# arduino_connector.net
KiCad netlist of a schematic drawn in Altium Designer
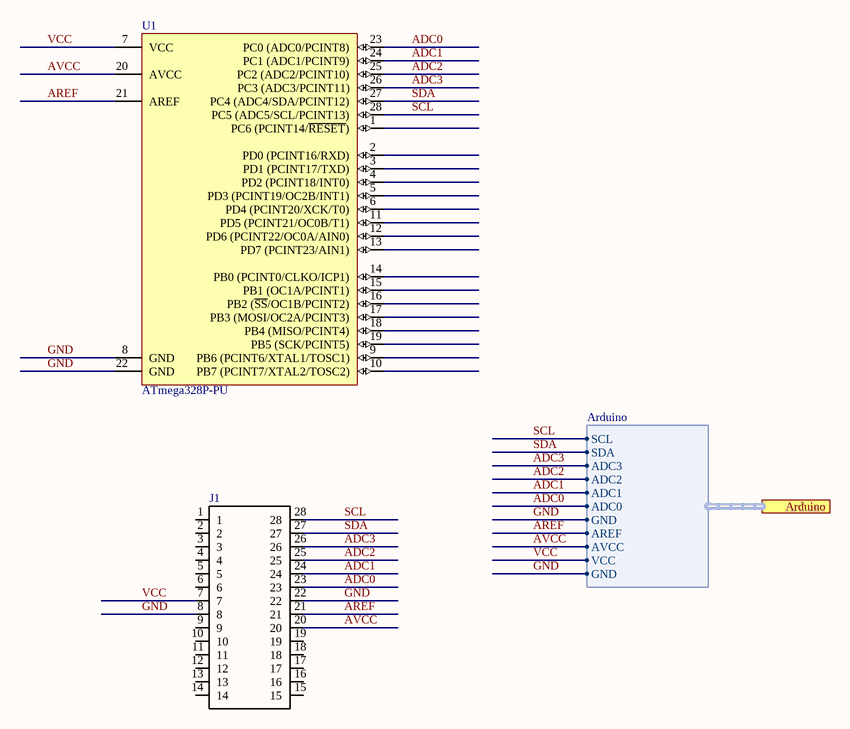
[diagram p0: arduino_connector.SchDoc]

(export (version "E")
  (design (tool "Eeschema 10.0.6"))
  (components
    (comp (ref "J1")
      (value "1-2199298-9")
      (footprint "*DIP762W60P254L3556H510Q28")
      (description "28P,DIP SKT,300 CL,LDR,PB FREE")
      (fields (field (name "DIGI-KEY_PART_NUMBER") "A120353-ND") (field (name "MF") "TE Connectivity"))
      (libsource (lib "1-2199298-9") (part "1-2199298-9"))
    )
    (comp (ref "U1")
      (value "ATmega328P-PU")
      (footprint "28P3")
      (libsource (lib "Altium Content Vault") (part "MC-8B-ATM48-IL28"))
    )
  )
  (nets
    (net (code "2") (name "/ADC0") (class "Default")
      (node (ref "J1") (pin "23") (pinfunction "23_23") (pintype "passive"))
      (node (ref "U1") (pin "23") (pinfunction "PC0_(ADC0/PCINT8)_23") (pintype "bidirectional"))
    )
    (net (code "3") (name "/ADC1") (class "Default")
      (node (ref "J1") (pin "24") (pinfunction "24_24") (pintype "passive"))
      (node (ref "U1") (pin "24") (pinfunction "PC1_(ADC1/PCINT9)_24") (pintype "bidirectional"))
    )
    (net (code "4") (name "/ADC2") (class "Default")
      (node (ref "J1") (pin "25") (pinfunction "25_25") (pintype "passive"))
      (node (ref "U1") (pin "25") (pinfunction "PC2_(ADC2/PCINT10)_25") (pintype "bidirectional"))
    )
    (net (code "5") (name "/ADC3") (class "Default")
      (node (ref "J1") (pin "26") (pinfunction "26_26") (pintype "passive"))
      (node (ref "U1") (pin "26") (pinfunction "PC3_(ADC3/PCINT11)_26") (pintype "bidirectional"))
    )
    (net (code "6") (name "/AREF") (class "Default")
      (node (ref "J1") (pin "21") (pinfunction "21_21") (pintype "passive"))
      (node (ref "U1") (pin "21") (pinfunction "AREF_21") (pintype "power_in"))
    )
    (net (code "7") (name "/AVCC") (class "Default")
      (node (ref "J1") (pin "20") (pinfunction "20_20") (pintype "passive"))
      (node (ref "U1") (pin "20") (pinfunction "AVCC_20") (pintype "power_in"))
    )
    (net (code "8") (name "/GND") (class "Default")
      (node (ref "J1") (pin "22") (pinfunction "22_22") (pintype "passive"))
      (node (ref "J1") (pin "8") (pinfunction "8_8") (pintype "passive"))
      (node (ref "U1") (pin "22") (pinfunction "GND_22") (pintype "power_in"))
      (node (ref "U1") (pin "8") (pinfunction "GND_8") (pintype "power_in"))
    )
    (net (code "9") (name "/SCL") (class "Default")
      (node (ref "J1") (pin "28") (pinfunction "28_28") (pintype "passive"))
      (node (ref "U1") (pin "28") (pinfunction "PC5_(ADC5/SCL/PCINT13)_28") (pintype "bidirectional"))
    )
    (net (code "10") (name "/SDA") (class "Default")
      (node (ref "J1") (pin "27") (pinfunction "27_27") (pintype "passive"))
      (node (ref "U1") (pin "27") (pinfunction "PC4_(ADC4/SDA/PCINT12)_27") (pintype "bidirectional"))
    )
    (net (code "11") (name "/VCC") (class "Default")
      (node (ref "J1") (pin "7") (pinfunction "7_7") (pintype "passive"))
      (node (ref "U1") (pin "7") (pinfunction "VCC_7") (pintype "power_in"))
    )
    (net (code "13") (name "unconnected-(J1-Pad1)") (class "Default")
      (node (ref "J1") (pin "1") (pinfunction "1_1") (pintype "passive"))
    )
    (net (code "14") (name "unconnected-(J1-Pad2)") (class "Default")
      (node (ref "J1") (pin "2") (pinfunction "2_2") (pintype "passive"))
    )
    (net (code "15") (name "unconnected-(J1-Pad3)") (class "Default")
      (node (ref "J1") (pin "3") (pinfunction "3_3") (pintype "passive"))
    )
    (net (code "16") (name "unconnected-(J1-Pad4)") (class "Default")
      (node (ref "J1") (pin "4") (pinfunction "4_4") (pintype "passive"))
    )
    (net (code "17") (name "unconnected-(J1-Pad5)") (class "Default")
      (node (ref "J1") (pin "5") (pinfunction "5_5") (pintype "passive"))
    )
    (net (code "18") (name "unconnected-(J1-Pad6)") (class "Default")
      (node (ref "J1") (pin "6") (pinfunction "6_6") (pintype "passive"))
    )
    (net (code "19") (name "unconnected-(J1-Pad9)") (class "Default")
      (node (ref "J1") (pin "9") (pinfunction "9_9") (pintype "passive"))
    )
    (net (code "20") (name "unconnected-(J1-Pad10)") (class "Default")
      (node (ref "J1") (pin "10") (pinfunction "10_10") (pintype "passive"))
    )
    (net (code "21") (name "unconnected-(J1-Pad11)") (class "Default")
      (node (ref "J1") (pin "11") (pinfunction "11_11") (pintype "passive"))
    )
    (net (code "22") (name "unconnected-(J1-Pad12)") (class "Default")
      (node (ref "J1") (pin "12") (pinfunction "12_12") (pintype "passive"))
    )
    (net (code "23") (name "unconnected-(J1-Pad13)") (class "Default")
      (node (ref "J1") (pin "13") (pinfunction "13_13") (pintype "passive"))
    )
    (net (code "24") (name "unconnected-(J1-Pad14)") (class "Default")
      (node (ref "J1") (pin "14") (pinfunction "14_14") (pintype "passive"))
    )
    (net (code "25") (name "unconnected-(J1-Pad15)") (class "Default")
      (node (ref "J1") (pin "15") (pinfunction "15_15") (pintype "passive"))
    )
    (net (code "26") (name "unconnected-(J1-Pad16)") (class "Default")
      (node (ref "J1") (pin "16") (pinfunction "16_16") (pintype "passive"))
    )
    (net (code "27") (name "unconnected-(J1-Pad17)") (class "Default")
      (node (ref "J1") (pin "17") (pinfunction "17_17") (pintype "passive"))
    )
    (net (code "28") (name "unconnected-(J1-Pad18)") (class "Default")
      (node (ref "J1") (pin "18") (pinfunction "18_18") (pintype "passive"))
    )
    (net (code "29") (name "unconnected-(J1-Pad19)") (class "Default")
      (node (ref "J1") (pin "19") (pinfunction "19_19") (pintype "passive"))
    )
    (net (code "30") (name "unconnected-(U1-PB0_(PCINT0{slash}CLKO{slash}ICP1)-Pad14)") (class "Default")
      (node (ref "U1") (pin "14") (pinfunction "PB0_(PCINT0/CLKO/ICP1)_14") (pintype "bidirectional"))
    )
    (net (code "31") (name "unconnected-(U1-PB1_(OC1A{slash}PCINT1)-Pad15)") (class "Default")
      (node (ref "U1") (pin "15") (pinfunction "PB1_(OC1A/PCINT1)_15") (pintype "bidirectional"))
    )
    (net (code "32") (name "unconnected-(U1-PB2_(~{SS}{slash}OC1B{slash}PCINT2)-Pad16)") (class "Default")
      (node (ref "U1") (pin "16") (pinfunction "PB2_(~{SS}/OC1B/PCINT2)_16") (pintype "bidirectional"))
    )
    (net (code "33") (name "unconnected-(U1-PB3_(MOSI{slash}OC2A{slash}PCINT3)-Pad17)") (class "Default")
      (node (ref "U1") (pin "17") (pinfunction "PB3_(MOSI/OC2A/PCINT3)_17") (pintype "bidirectional"))
    )
    (net (code "34") (name "unconnected-(U1-PB4_(MISO{slash}PCINT4)-Pad18)") (class "Default")
      (node (ref "U1") (pin "18") (pinfunction "PB4_(MISO/PCINT4)_18") (pintype "bidirectional"))
    )
    (net (code "35") (name "unconnected-(U1-PB5_(SCK{slash}PCINT5)-Pad19)") (class "Default")
      (node (ref "U1") (pin "19") (pinfunction "PB5_(SCK/PCINT5)_19") (pintype "bidirectional"))
    )
    (net (code "36") (name "unconnected-(U1-PB6_(PCINT6{slash}XTAL1{slash}TOSC1)-Pad9)") (class "Default")
      (node (ref "U1") (pin "9") (pinfunction "PB6_(PCINT6/XTAL1/TOSC1)_9") (pintype "bidirectional"))
    )
    (net (code "37") (name "unconnected-(U1-PB7_(PCINT7{slash}XTAL2{slash}TOSC2)-Pad10)") (class "Default")
      (node (ref "U1") (pin "10") (pinfunction "PB7_(PCINT7/XTAL2/TOSC2)_10") (pintype "bidirectional"))
    )
    (net (code "38") (name "unconnected-(U1-PC6_(PCINT14{slash}~{RESET})-Pad1)") (class "Default")
      (node (ref "U1") (pin "1") (pinfunction "PC6_(PCINT14/~{RESET})_1") (pintype "bidirectional"))
    )
    (net (code "39") (name "unconnected-(U1-PD0_(PCINT16{slash}RXD)-Pad2)") (class "Default")
      (node (ref "U1") (pin "2") (pinfunction "PD0_(PCINT16/RXD)_2") (pintype "bidirectional"))
    )
    (net (code "40") (name "unconnected-(U1-PD1_(PCINT17{slash}TXD)-Pad3)") (class "Default")
      (node (ref "U1") (pin "3") (pinfunction "PD1_(PCINT17/TXD)_3") (pintype "bidirectional"))
    )
    (net (code "41") (name "unconnected-(U1-PD2_(PCINT18{slash}INT0)-Pad4)") (class "Default")
      (node (ref "U1") (pin "4") (pinfunction "PD2_(PCINT18/INT0)_4") (pintype "bidirectional"))
    )
    (net (code "42") (name "unconnected-(U1-PD3_(PCINT19{slash}OC2B{slash}INT1)-Pad5)") (class "Default")
      (node (ref "U1") (pin "5") (pinfunction "PD3_(PCINT19/OC2B/INT1)_5") (pintype "bidirectional"))
    )
    (net (code "43") (name "unconnected-(U1-PD4_(PCINT20{slash}XCK{slash}T0)-Pad6)") (class "Default")
      (node (ref "U1") (pin "6") (pinfunction "PD4_(PCINT20/XCK/T0)_6") (pintype "bidirectional"))
    )
    (net (code "44") (name "unconnected-(U1-PD5_(PCINT21{slash}OC0B{slash}T1)-Pad11)") (class "Default")
      (node (ref "U1") (pin "11") (pinfunction "PD5_(PCINT21/OC0B/T1)_11") (pintype "bidirectional"))
    )
    (net (code "45") (name "unconnected-(U1-PD6_(PCINT22{slash}OC0A{slash}AIN0)-Pad12)") (class "Default")
      (node (ref "U1") (pin "12") (pinfunction "PD6_(PCINT22/OC0A/AIN0)_12") (pintype "bidirectional"))
    )
    (net (code "46") (name "unconnected-(U1-PD7_(PCINT23{slash}AIN1)-Pad13)") (class "Default")
      (node (ref "U1") (pin "13") (pinfunction "PD7_(PCINT23/AIN1)_13") (pintype "bidirectional"))
    )
  )
)
